# Remote_Board_V1_0.net
KiCad netlist of a schematic drawn in EAGLE
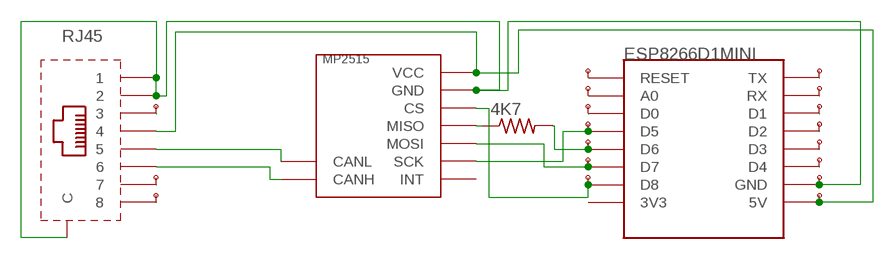
[diagram p0: schematic, sheet 1]

(export (version "E")
  (design (tool "Eeschema 10.0.6"))
  (components
    (comp (ref "4K7")
      (value "R-US_0207/10")
      (footprint "eagle-import:0207_10")
      (libsource (lib "eagle-import") (part "R-US_0207/10"))
    )
    (comp (ref "ESP8266D1MINI")
      (value "WEMOS-D1-MINI_SEM_LAYOUT")
      (footprint "eagle-import:WEMOS-D1-MINI_SEM_LAYOUT")
      (libsource (lib "eagle-import") (part "WEMOS-D1-MINI_SEM_LAYOUT"))
    )
    (comp (ref "RJ45")
      (value "ALI-RJ45_SEM_LAYOUT")
      (footprint "eagle-import:ALI-RJ45_SEM_LAYOUT")
      (libsource (lib "eagle-import") (part "ALI-RJ45_SEM_LAYOUT"))
    )
    (comp (ref "U$1") (value "TP") (footprint "eagle-import:TP") (libsource (lib "eagle-import") (part "TP")))
    (comp (ref "U$2") (value "TP") (footprint "eagle-import:TP") (libsource (lib "eagle-import") (part "TP")))
    (comp (ref "U$3") (value "TP") (footprint "eagle-import:TP") (libsource (lib "eagle-import") (part "TP")))
    (comp (ref "U$4") (value "TP") (footprint "eagle-import:TP") (libsource (lib "eagle-import") (part "TP")))
    (comp (ref "U$5") (value "TP") (footprint "eagle-import:TP") (libsource (lib "eagle-import") (part "TP")))
    (comp (ref "U$6") (value "TP") (footprint "eagle-import:TP") (libsource (lib "eagle-import") (part "TP")))
    (comp (ref "U$7") (value "TP") (footprint "eagle-import:TP") (libsource (lib "eagle-import") (part "TP")))
    (comp (ref "U$8") (value "TP") (footprint "eagle-import:TP") (libsource (lib "eagle-import") (part "TP")))
    (comp (ref "U$9") (value "TP") (footprint "eagle-import:TP") (libsource (lib "eagle-import") (part "TP")))
    (comp (ref "U$10")
      (value "TP")
      (footprint "eagle-import:TP")
      (libsource (lib "eagle-import") (part "TP"))
    )
    (comp (ref "U$11")
      (value "TP")
      (footprint "eagle-import:TP")
      (libsource (lib "eagle-import") (part "TP"))
    )
    (comp (ref "U$12")
      (value "TP")
      (footprint "eagle-import:TP")
      (libsource (lib "eagle-import") (part "TP"))
    )
    (comp (ref "U$13")
      (value "TP")
      (footprint "eagle-import:TP")
      (libsource (lib "eagle-import") (part "TP"))
    )
    (comp (ref "U$14")
      (value "TP")
      (footprint "eagle-import:TP")
      (libsource (lib "eagle-import") (part "TP"))
    )
    (comp (ref "U$15")
      (value "TP")
      (footprint "eagle-import:TP")
      (libsource (lib "eagle-import") (part "TP"))
    )
    (comp (ref "U$16")
      (value "TP")
      (footprint "eagle-import:TP")
      (libsource (lib "eagle-import") (part "TP"))
    )
    (comp (ref "U$17")
      (value "TP")
      (footprint "eagle-import:TP")
      (libsource (lib "eagle-import") (part "TP"))
    )
    (comp (ref "U$18")
      (value "TP")
      (footprint "eagle-import:TP")
      (libsource (lib "eagle-import") (part "TP"))
    )
    (comp (ref "U$31")
      (value "MCP2515_MODULE_SEM_LAYOUT")
      (footprint "eagle-import:MCP2515_MODULE_SEM_LAYOUT")
      (libsource (lib "eagle-import") (part "MCP2515_MODULE_SEM_LAYOUT"))
    )
  )
  (nets
    (net (code "1") (name "Net-(4K7-Pad1)") (class "Default")
      (node (ref "4K7") (pin "1") (pinfunction "1_1") (pintype "passive"))
      (node (ref "U$31") (pin "MISO") (pinfunction "MISO_MISO") (pintype "bidirectional"))
    )
    (net (code "2") (name "Net-(4K7-Pad2)") (class "Default")
      (node (ref "4K7") (pin "2") (pinfunction "2_2") (pintype "passive"))
      (node (ref "ESP8266D1MINI") (pin "D6") (pinfunction "D6_D6") (pintype "bidirectional"))
      (node (ref "U$5") (pin "P$1") (pinfunction "P$1_P$1") (pintype "bidirectional"))
    )
    (net (code "3") (name "Net-(ESP8266D1MINI-Pad5V)") (class "Default")
      (node (ref "ESP8266D1MINI") (pin "5V") (pinfunction "5V_5V") (pintype "bidirectional"))
      (node (ref "RJ45") (pin "4") (pinfunction "4_4") (pintype "bidirectional"))
      (node (ref "U$16") (pin "P$1") (pinfunction "P$1_P$1") (pintype "bidirectional"))
      (node (ref "U$31") (pin "VCC") (pinfunction "VCC_VCC") (pintype "bidirectional"))
    )
    (net (code "4") (name "Net-(ESP8266D1MINI-PadA0)") (class "Default")
      (node (ref "ESP8266D1MINI") (pin "A0") (pinfunction "A0_A0") (pintype "bidirectional"))
      (node (ref "U$2") (pin "P$1") (pinfunction "P$1_P$1") (pintype "bidirectional"))
    )
    (net (code "5") (name "Net-(ESP8266D1MINI-PadD0)") (class "Default")
      (node (ref "ESP8266D1MINI") (pin "D0") (pinfunction "D0_D0") (pintype "bidirectional"))
      (node (ref "U$3") (pin "P$1") (pinfunction "P$1_P$1") (pintype "bidirectional"))
    )
    (net (code "6") (name "Net-(ESP8266D1MINI-PadD1)") (class "Default")
      (node (ref "ESP8266D1MINI") (pin "D1") (pinfunction "D1_D1") (pintype "bidirectional"))
      (node (ref "U$11") (pin "P$1") (pinfunction "P$1_P$1") (pintype "bidirectional"))
    )
    (net (code "7") (name "Net-(ESP8266D1MINI-PadD2)") (class "Default")
      (node (ref "ESP8266D1MINI") (pin "D2") (pinfunction "D2_D2") (pintype "bidirectional"))
      (node (ref "U$12") (pin "P$1") (pinfunction "P$1_P$1") (pintype "bidirectional"))
    )
    (net (code "8") (name "Net-(ESP8266D1MINI-PadD3)") (class "Default")
      (node (ref "ESP8266D1MINI") (pin "D3") (pinfunction "D3_D3") (pintype "bidirectional"))
      (node (ref "U$13") (pin "P$1") (pinfunction "P$1_P$1") (pintype "bidirectional"))
    )
    (net (code "9") (name "Net-(ESP8266D1MINI-PadD4)") (class "Default")
      (node (ref "ESP8266D1MINI") (pin "D4") (pinfunction "D4_D4") (pintype "bidirectional"))
      (node (ref "U$14") (pin "P$1") (pinfunction "P$1_P$1") (pintype "bidirectional"))
    )
    (net (code "10") (name "Net-(ESP8266D1MINI-PadD5)") (class "Default")
      (node (ref "ESP8266D1MINI") (pin "D5") (pinfunction "D5_D5") (pintype "bidirectional"))
      (node (ref "U$31") (pin "SCK") (pinfunction "SCK_SCK") (pintype "bidirectional"))
      (node (ref "U$4") (pin "P$1") (pinfunction "P$1_P$1") (pintype "bidirectional"))
    )
    (net (code "11") (name "Net-(ESP8266D1MINI-PadD7)") (class "Default")
      (node (ref "ESP8266D1MINI") (pin "D7") (pinfunction "D7_D7") (pintype "bidirectional"))
      (node (ref "U$31") (pin "MOSI") (pinfunction "MOSI_MOSI") (pintype "bidirectional"))
      (node (ref "U$8") (pin "P$1") (pinfunction "P$1_P$1") (pintype "bidirectional"))
    )
    (net (code "12") (name "Net-(ESP8266D1MINI-PadD8)") (class "Default")
      (node (ref "ESP8266D1MINI") (pin "D8") (pinfunction "D8_D8") (pintype "bidirectional"))
      (node (ref "U$31") (pin "CS") (pinfunction "CS_CS") (pintype "bidirectional"))
      (node (ref "U$9") (pin "P$1") (pinfunction "P$1_P$1") (pintype "bidirectional"))
    )
    (net (code "13") (name "Net-(ESP8266D1MINI-PadGND)") (class "Default")
      (node (ref "ESP8266D1MINI") (pin "GND") (pinfunction "GND_GND") (pintype "bidirectional"))
      (node (ref "RJ45") (pin "1") (pinfunction "1_1") (pintype "bidirectional"))
      (node (ref "RJ45") (pin "2") (pinfunction "2_2") (pintype "bidirectional"))
      (node (ref "RJ45") (pin "P$1") (pinfunction "C_P$1") (pintype "bidirectional"))
      (node (ref "RJ45") (pin "P$2") (pinfunction "C_P$2") (pintype "bidirectional"))
      (node (ref "U$15") (pin "P$1") (pinfunction "P$1_P$1") (pintype "bidirectional"))
      (node (ref "U$31") (pin "GND") (pinfunction "GND_GND") (pintype "bidirectional"))
    )
    (net (code "14") (name "Net-(ESP8266D1MINI-PadRESET)") (class "Default")
      (node (ref "ESP8266D1MINI") (pin "RESET") (pinfunction "RESET_RESET") (pintype "bidirectional"))
      (node (ref "U$1") (pin "P$1") (pinfunction "P$1_P$1") (pintype "bidirectional"))
    )
    (net (code "15") (name "Net-(ESP8266D1MINI-PadRX)") (class "Default")
      (node (ref "ESP8266D1MINI") (pin "RX") (pinfunction "RX_RX") (pintype "bidirectional"))
      (node (ref "U$7") (pin "P$1") (pinfunction "P$1_P$1") (pintype "bidirectional"))
    )
    (net (code "16") (name "Net-(ESP8266D1MINI-PadTX)") (class "Default")
      (node (ref "ESP8266D1MINI") (pin "TX") (pinfunction "TX_TX") (pintype "bidirectional"))
      (node (ref "U$6") (pin "P$1") (pinfunction "P$1_P$1") (pintype "bidirectional"))
    )
    (net (code "17") (name "Net-(RJ45-Pad3)") (class "Default")
      (node (ref "RJ45") (pin "3") (pinfunction "3_3") (pintype "bidirectional"))
      (node (ref "U$10") (pin "P$1") (pinfunction "P$1_P$1") (pintype "bidirectional"))
    )
    (net (code "18") (name "Net-(RJ45-Pad7)") (class "Default")
      (node (ref "RJ45") (pin "7") (pinfunction "7_7") (pintype "bidirectional"))
      (node (ref "U$17") (pin "P$1") (pinfunction "P$1_P$1") (pintype "bidirectional"))
    )
    (net (code "19") (name "Net-(RJ45-Pad8)") (class "Default")
      (node (ref "RJ45") (pin "8") (pinfunction "8_8") (pintype "bidirectional"))
      (node (ref "U$18") (pin "P$1") (pinfunction "P$1_P$1") (pintype "bidirectional"))
    )
    (net (code "20") (name "Net-(U$31-CANH)") (class "Default")
      (node (ref "RJ45") (pin "6") (pinfunction "6_6") (pintype "bidirectional"))
      (node (ref "U$31") (pin "CH") (pinfunction "CANH_CH") (pintype "bidirectional"))
    )
    (net (code "21") (name "Net-(U$31-CANL)") (class "Default")
      (node (ref "RJ45") (pin "5") (pinfunction "5_5") (pintype "bidirectional"))
      (node (ref "U$31") (pin "CL") (pinfunction "CANL_CL") (pintype "bidirectional"))
    )
    (net (code "22") (name "unconnected-(ESP8266D1MINI-Pad3V3)") (class "Default")
      (node (ref "ESP8266D1MINI") (pin "3V3") (pinfunction "3V3_3V3") (pintype "bidirectional"))
    )
    (net (code "23") (name "unconnected-(U$31-PadINT)") (class "Default")
      (node (ref "U$31") (pin "INT") (pinfunction "INT_INT") (pintype "bidirectional"))
    )
  )
)
